# Sheet1.net
KiCad netlist of a schematic drawn in Altium Designer
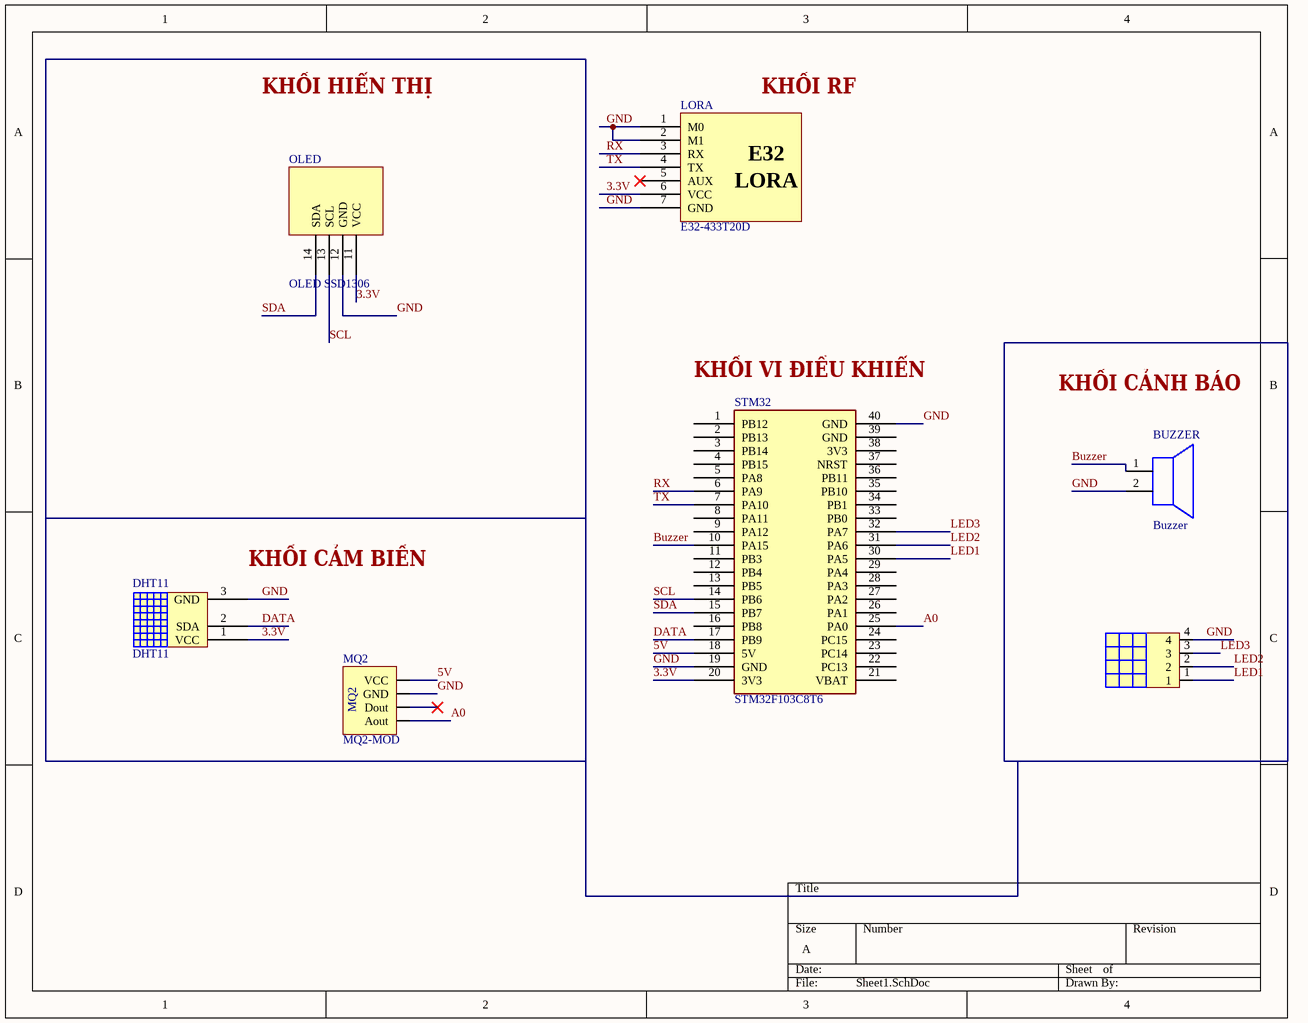
[diagram p0: Sheet1.SchDoc]

(export (version "E")
  (design (tool "Eeschema 10.0.6"))
  (components
    (comp (ref "BUZZER") (value "Buzzer") (footprint "speaker") (libsource (lib "Symbol") (part "Buzzer")))
    (comp (ref "DHT11")
      (value "DHT11")
      (footprint "DHT11_KIT")
      (libsource (lib "MYHGBLIB_SCH") (part "DHT11"))
    )
    (comp (ref "LED")
      (value "Dht22")
      (footprint "JST_B4B-XH-A")
      (description "Header, 4-Pin")
      (fields (field (name "PUBLISHER") "Altium Limited"))
      (libsource (lib "Symbol") (part "Dht22"))
    )
    (comp (ref "LORA")
      (value "E32-433T20D")
      (footprint "LORA_E32")
      (libsource (lib "MYHGBLIB_SCH") (part "Lora E32-433T20D"))
    )
    (comp (ref "MQ2")
      (value "MQ2-MOD")
      (footprint "JST_B4B-XH-A")
      (fields
        (field (name "MANUFACTURER") "Würth Elektronik eiSos GmbH")
        (field (name "PARTNO") "613004143121")
        (field (name "CREATED BY") "Karrer Zheng")
      )
      (libsource (lib "Symbol") (part "MQ2-MOD"))
    )
    (comp (ref "OLED") (value "OLED SSD1306") (footprint "OLED") (libsource (lib "Symbol") (part "SSD1306")))
    (comp (ref "STM32")
      (value "STM32F103C8T6")
      (footprint "Stm32 BluePill")
      (description "Designed By @Alixahedi")
      (libsource (lib "Symbol") (part "BluePill"))
    )
  )
  (nets
    (net (code "1") (name "/3.3V") (class "Default")
      (node (ref "DHT11") (pin "1") (pinfunction "VCC_1") (pintype "passive"))
      (node (ref "LORA") (pin "6") (pinfunction "VCC_6") (pintype "passive"))
      (node (ref "OLED") (pin "11") (pinfunction "VCC_11") (pintype "passive"))
      (node (ref "STM32") (pin "20") (pinfunction "3V3_20") (pintype "passive"))
    )
    (net (code "2") (name "/5V") (class "Default")
      (node (ref "MQ2") (pin "4") (pinfunction "VCC_4") (pintype "passive"))
      (node (ref "STM32") (pin "18") (pinfunction "5V_18") (pintype "passive"))
    )
    (net (code "3") (name "/A0") (class "Default")
      (node (ref "MQ2") (pin "1") (pinfunction "Aout_1") (pintype "passive"))
      (node (ref "STM32") (pin "25") (pinfunction "PA0_25") (pintype "passive"))
    )
    (net (code "4") (name "/Buzzer") (class "Default")
      (node (ref "BUZZER") (pin "1") (pinfunction "+_1") (pintype "passive"))
      (node (ref "STM32") (pin "10") (pinfunction "PA15_10") (pintype "passive"))
    )
    (net (code "5") (name "/DATA") (class "Default")
      (node (ref "DHT11") (pin "2") (pinfunction "SDA_2") (pintype "passive"))
      (node (ref "STM32") (pin "17") (pinfunction "PB9_17") (pintype "passive"))
    )
    (net (code "6") (name "/GND") (class "Default")
      (node (ref "BUZZER") (pin "2") (pinfunction "-_2") (pintype "passive"))
      (node (ref "DHT11") (pin "3") (pinfunction "GND_3") (pintype "passive"))
      (node (ref "LED") (pin "4") (pinfunction "4_4") (pintype "passive"))
      (node (ref "LORA") (pin "1") (pinfunction "M0_1") (pintype "passive"))
      (node (ref "LORA") (pin "2") (pinfunction "M1_2") (pintype "passive"))
      (node (ref "LORA") (pin "7") (pinfunction "GND_7") (pintype "passive"))
      (node (ref "MQ2") (pin "3") (pinfunction "GND_3") (pintype "passive"))
      (node (ref "OLED") (pin "12") (pinfunction "GND_12") (pintype "passive"))
      (node (ref "STM32") (pin "19") (pinfunction "GND_19") (pintype "passive"))
      (node (ref "STM32") (pin "40") (pinfunction "GND_40") (pintype "passive"))
    )
    (net (code "7") (name "/LED1") (class "Default")
      (node (ref "LED") (pin "1") (pinfunction "1_1") (pintype "passive"))
      (node (ref "STM32") (pin "30") (pinfunction "PA5_30") (pintype "passive"))
    )
    (net (code "8") (name "/LED2") (class "Default")
      (node (ref "LED") (pin "2") (pinfunction "2_2") (pintype "passive"))
      (node (ref "STM32") (pin "31") (pinfunction "PA6_31") (pintype "passive"))
    )
    (net (code "9") (name "/LED3") (class "Default")
      (node (ref "LED") (pin "3") (pinfunction "3_3") (pintype "passive"))
      (node (ref "STM32") (pin "32") (pinfunction "PA7_32") (pintype "passive"))
    )
    (net (code "10") (name "/RX") (class "Default")
      (node (ref "LORA") (pin "3") (pinfunction "RX_3") (pintype "passive"))
      (node (ref "STM32") (pin "6") (pinfunction "PA9_6") (pintype "passive"))
    )
    (net (code "11") (name "/SCL") (class "Default")
      (node (ref "OLED") (pin "13") (pinfunction "SCL_13") (pintype "passive"))
      (node (ref "STM32") (pin "14") (pinfunction "PB6_14") (pintype "passive"))
    )
    (net (code "12") (name "/SDA") (class "Default")
      (node (ref "OLED") (pin "14") (pinfunction "SDA_14") (pintype "passive"))
      (node (ref "STM32") (pin "15") (pinfunction "PB7_15") (pintype "passive"))
    )
    (net (code "13") (name "/TX") (class "Default")
      (node (ref "LORA") (pin "4") (pinfunction "TX_4") (pintype "passive"))
      (node (ref "STM32") (pin "7") (pinfunction "PA10_7") (pintype "passive"))
    )
    (net (code "14") (name "unconnected-(LORA-AUX-Pad5)") (class "Default")
      (node (ref "LORA") (pin "5") (pinfunction "AUX_5") (pintype "passive+no_connect"))
    )
    (net (code "15") (name "unconnected-(MQ2-Dout-Pad2)") (class "Default")
      (node (ref "MQ2") (pin "2") (pinfunction "Dout_2") (pintype "passive+no_connect"))
    )
    (net (code "16") (name "unconnected-(STM32-3V3-Pad38)") (class "Default")
      (node (ref "STM32") (pin "38") (pinfunction "3V3_38") (pintype "passive"))
    )
    (net (code "17") (name "unconnected-(STM32-GND-Pad39)") (class "Default")
      (node (ref "STM32") (pin "39") (pinfunction "GND_39") (pintype "passive"))
    )
    (net (code "18") (name "unconnected-(STM32-NRST-Pad37)") (class "Default")
      (node (ref "STM32") (pin "37") (pinfunction "NRST_37") (pintype "passive"))
    )
    (net (code "19") (name "unconnected-(STM32-PA1-Pad26)") (class "Default")
      (node (ref "STM32") (pin "26") (pinfunction "PA1_26") (pintype "passive"))
    )
    (net (code "20") (name "unconnected-(STM32-PA2-Pad27)") (class "Default")
      (node (ref "STM32") (pin "27") (pinfunction "PA2_27") (pintype "passive"))
    )
    (net (code "21") (name "unconnected-(STM32-PA3-Pad28)") (class "Default")
      (node (ref "STM32") (pin "28") (pinfunction "PA3_28") (pintype "passive"))
    )
    (net (code "22") (name "unconnected-(STM32-PA4-Pad29)") (class "Default")
      (node (ref "STM32") (pin "29") (pinfunction "PA4_29") (pintype "passive"))
    )
    (net (code "23") (name "unconnected-(STM32-PA8-Pad5)") (class "Default")
      (node (ref "STM32") (pin "5") (pinfunction "PA8_5") (pintype "passive"))
    )
    (net (code "24") (name "unconnected-(STM32-PA11-Pad8)") (class "Default")
      (node (ref "STM32") (pin "8") (pinfunction "PA11_8") (pintype "passive"))
    )
    (net (code "25") (name "unconnected-(STM32-PA12-Pad9)") (class "Default")
      (node (ref "STM32") (pin "9") (pinfunction "PA12_9") (pintype "passive"))
    )
    (net (code "26") (name "unconnected-(STM32-PB0-Pad33)") (class "Default")
      (node (ref "STM32") (pin "33") (pinfunction "PB0_33") (pintype "passive"))
    )
    (net (code "27") (name "unconnected-(STM32-PB1-Pad34)") (class "Default")
      (node (ref "STM32") (pin "34") (pinfunction "PB1_34") (pintype "passive"))
    )
    (net (code "28") (name "unconnected-(STM32-PB3-Pad11)") (class "Default")
      (node (ref "STM32") (pin "11") (pinfunction "PB3_11") (pintype "passive"))
    )
    (net (code "29") (name "unconnected-(STM32-PB4-Pad12)") (class "Default")
      (node (ref "STM32") (pin "12") (pinfunction "PB4_12") (pintype "passive"))
    )
    (net (code "30") (name "unconnected-(STM32-PB5-Pad13)") (class "Default")
      (node (ref "STM32") (pin "13") (pinfunction "PB5_13") (pintype "passive"))
    )
    (net (code "31") (name "unconnected-(STM32-PB8-Pad16)") (class "Default")
      (node (ref "STM32") (pin "16") (pinfunction "PB8_16") (pintype "passive"))
    )
    (net (code "32") (name "unconnected-(STM32-PB10-Pad35)") (class "Default")
      (node (ref "STM32") (pin "35") (pinfunction "PB10_35") (pintype "passive"))
    )
    (net (code "33") (name "unconnected-(STM32-PB11-Pad36)") (class "Default")
      (node (ref "STM32") (pin "36") (pinfunction "PB11_36") (pintype "passive"))
    )
    (net (code "34") (name "unconnected-(STM32-PB12-Pad1)") (class "Default")
      (node (ref "STM32") (pin "1") (pinfunction "PB12_1") (pintype "passive"))
    )
    (net (code "35") (name "unconnected-(STM32-PB13-Pad2)") (class "Default")
      (node (ref "STM32") (pin "2") (pinfunction "PB13_2") (pintype "passive"))
    )
    (net (code "36") (name "unconnected-(STM32-PB14-Pad3)") (class "Default")
      (node (ref "STM32") (pin "3") (pinfunction "PB14_3") (pintype "passive"))
    )
    (net (code "37") (name "unconnected-(STM32-PB15-Pad4)") (class "Default")
      (node (ref "STM32") (pin "4") (pinfunction "PB15_4") (pintype "passive"))
    )
    (net (code "38") (name "unconnected-(STM32-PC13-Pad22)") (class "Default")
      (node (ref "STM32") (pin "22") (pinfunction "PC13_22") (pintype "passive"))
    )
    (net (code "39") (name "unconnected-(STM32-PC14-Pad23)") (class "Default")
      (node (ref "STM32") (pin "23") (pinfunction "PC14_23") (pintype "passive"))
    )
    (net (code "40") (name "unconnected-(STM32-PC15-Pad24)") (class "Default")
      (node (ref "STM32") (pin "24") (pinfunction "PC15_24") (pintype "passive"))
    )
    (net (code "41") (name "unconnected-(STM32-VBAT-Pad21)") (class "Default")
      (node (ref "STM32") (pin "21") (pinfunction "VBAT_21") (pintype "passive"))
    )
  )
)
